# ESP8266.net
KiCad netlist of a schematic drawn in Altium Designer
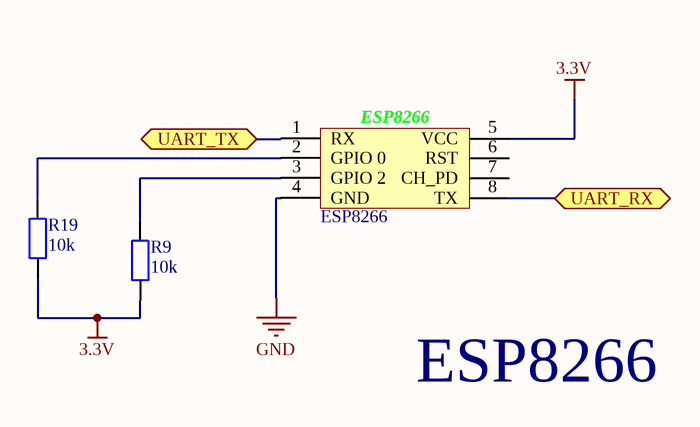
[diagram p0: ESP8266.SchDoc]

(export (version "E")
  (design (tool "Eeschema 10.0.6"))
  (components
    (comp (ref "ESP8266")
      (value "ESP8266 Module")
      (footprint "ESP2866 Module")
      (libsource (lib "Altium_Lib_by_KhueNguyenCreator") (part "ESP8266 Module"))
    )
    (comp (ref "R9")
      (value "10k")
      (footprint "tro smd 0603")
      (description "Dán")
      (libsource (lib "Altium_Lib_by_KhueNguyenCreator") (part "Tro 0603 5% 10k"))
    )
    (comp (ref "R19")
      (value "10k")
      (footprint "tro smd 0603")
      (description "Dán")
      (libsource (lib "Altium_Lib_by_KhueNguyenCreator") (part "Tro 0603 5% 10k"))
    )
  )
  (nets
    (net (code "1") (name "/UART_RX") (class "Default")
      (node (ref "ESP8266") (pin "8") (pinfunction "TX_8") (pintype "passive"))
    )
    (net (code "2") (name "/UART_TX") (class "Default")
      (node (ref "ESP8266") (pin "1") (pinfunction "RX_1") (pintype "passive"))
    )
    (net (code "3") (name "3.3V") (class "Default")
      (node (ref "ESP8266") (pin "5") (pinfunction "VCC_5") (pintype "passive"))
      (node (ref "R19") (pin "1") (pinfunction "1_1") (pintype "passive"))
      (node (ref "R9") (pin "1") (pinfunction "1_1") (pintype "passive"))
    )
    (net (code "4") (name "GND") (class "Default")
      (node (ref "ESP8266") (pin "4") (pinfunction "GND_4") (pintype "passive"))
    )
    (net (code "5") (name "Net-(ESP8266-GPIO_0)") (class "Default")
      (node (ref "ESP8266") (pin "2") (pinfunction "GPIO_0_2") (pintype "passive"))
      (node (ref "R19") (pin "2") (pinfunction "2_2") (pintype "passive"))
    )
    (net (code "6") (name "Net-(ESP8266-GPIO_2)") (class "Default")
      (node (ref "ESP8266") (pin "3") (pinfunction "GPIO_2_3") (pintype "passive"))
      (node (ref "R9") (pin "2") (pinfunction "2_2") (pintype "passive"))
    )
    (net (code "7") (name "unconnected-(ESP8266-CH_PD-Pad7)") (class "Default")
      (node (ref "ESP8266") (pin "7") (pinfunction "CH_PD_7") (pintype "passive"))
    )
    (net (code "8") (name "unconnected-(ESP8266-RST-Pad6)") (class "Default")
      (node (ref "ESP8266") (pin "6") (pinfunction "RST_6") (pintype "passive"))
    )
  )
)
